# M594X.net
KiCad netlist of a schematic drawn in EAGLE
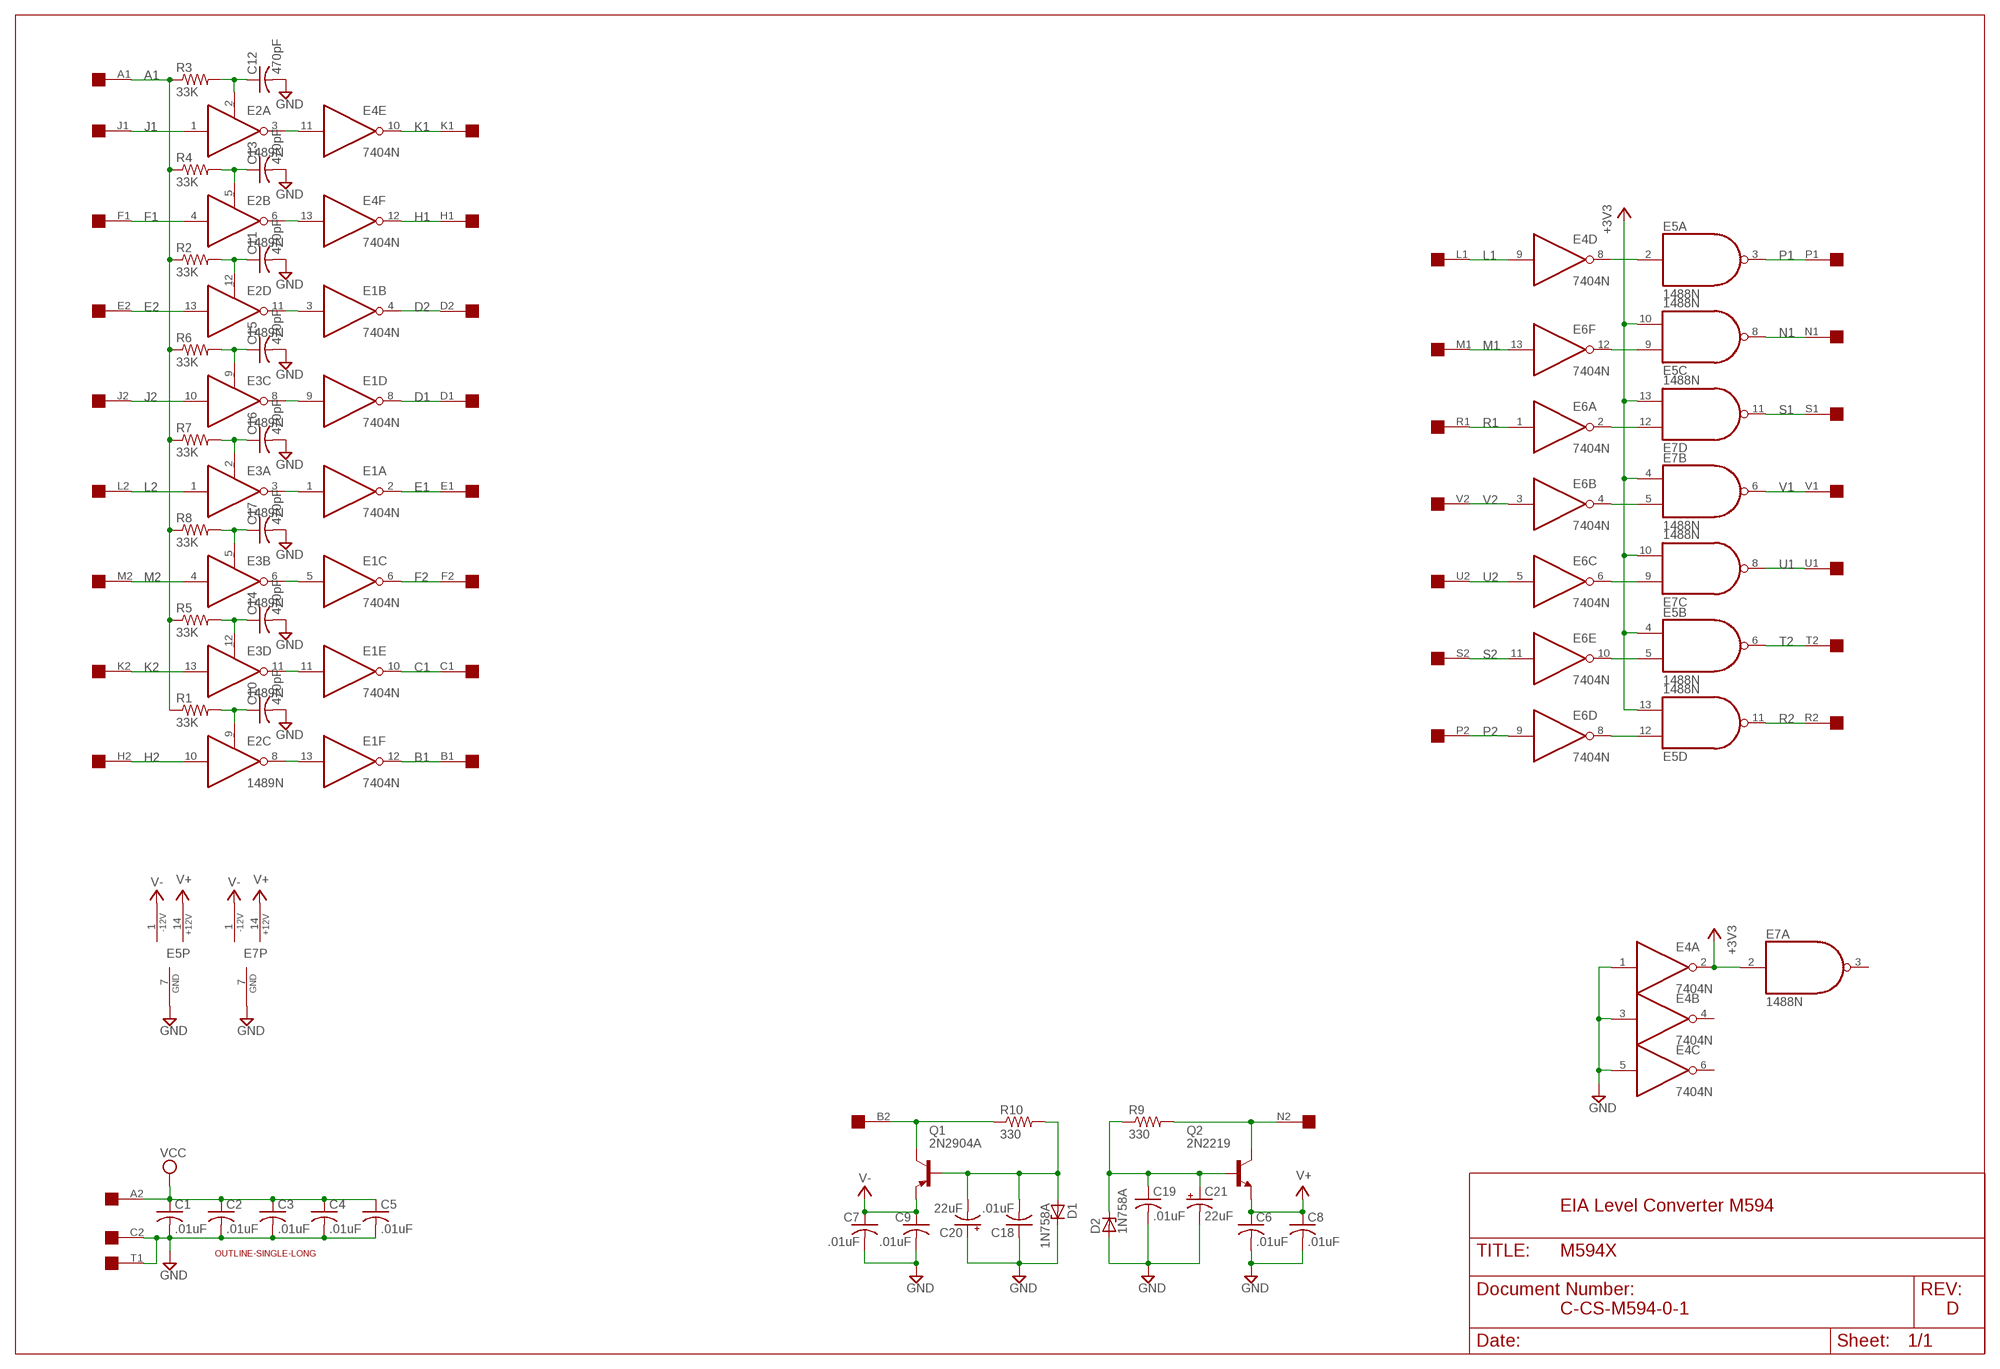
[diagram p0: schematic, sheet 1]

(export (version "E")
  (design (tool "Eeschema 10.0.6"))
  (components
    (comp (ref "C1")
      (value ".01uF")
      (footprint "eagle-import:C050-025X075")
      (libsource (lib "eagle-import") (part "C-US050-025X075"))
    )
    (comp (ref "C2")
      (value ".01uF")
      (footprint "eagle-import:C050-025X075")
      (libsource (lib "eagle-import") (part "C-US050-025X075"))
    )
    (comp (ref "C3")
      (value ".01uF")
      (footprint "eagle-import:C050-025X075")
      (libsource (lib "eagle-import") (part "C-US050-025X075"))
    )
    (comp (ref "C4")
      (value ".01uF")
      (footprint "eagle-import:C050-025X075")
      (libsource (lib "eagle-import") (part "C-US050-025X075"))
    )
    (comp (ref "C5")
      (value ".01uF")
      (footprint "eagle-import:C050-025X075")
      (libsource (lib "eagle-import") (part "C-US050-025X075"))
    )
    (comp (ref "C6")
      (value ".01uF")
      (footprint "eagle-import:C050-025X075")
      (libsource (lib "eagle-import") (part "C-US050-025X075"))
    )
    (comp (ref "C7")
      (value ".01uF")
      (footprint "eagle-import:C050-025X075")
      (libsource (lib "eagle-import") (part "C-US050-025X075"))
    )
    (comp (ref "C8")
      (value ".01uF")
      (footprint "eagle-import:C050-025X075")
      (libsource (lib "eagle-import") (part "C-US050-025X075"))
    )
    (comp (ref "C9")
      (value ".01uF")
      (footprint "eagle-import:C050-025X075")
      (libsource (lib "eagle-import") (part "C-US050-025X075"))
    )
    (comp (ref "C10")
      (value "470pF")
      (footprint "eagle-import:C075-032X103")
      (libsource (lib "eagle-import") (part "C-US075-032X103"))
    )
    (comp (ref "C11")
      (value "470pF")
      (footprint "eagle-import:C075-032X103")
      (libsource (lib "eagle-import") (part "C-US075-032X103"))
    )
    (comp (ref "C12")
      (value "470pF")
      (footprint "eagle-import:C075-032X103")
      (libsource (lib "eagle-import") (part "C-US075-032X103"))
    )
    (comp (ref "C13")
      (value "470pF")
      (footprint "eagle-import:C075-032X103")
      (libsource (lib "eagle-import") (part "C-US075-032X103"))
    )
    (comp (ref "C14")
      (value "470pF")
      (footprint "eagle-import:C075-032X103")
      (libsource (lib "eagle-import") (part "C-US075-032X103"))
    )
    (comp (ref "C15")
      (value "470pF")
      (footprint "eagle-import:C075-032X103")
      (libsource (lib "eagle-import") (part "C-US075-032X103"))
    )
    (comp (ref "C16")
      (value "470pF")
      (footprint "eagle-import:C075-032X103")
      (libsource (lib "eagle-import") (part "C-US075-032X103"))
    )
    (comp (ref "C17")
      (value "470pF")
      (footprint "eagle-import:C075-032X103")
      (libsource (lib "eagle-import") (part "C-US075-032X103"))
    )
    (comp (ref "C18")
      (value ".01uF")
      (footprint "eagle-import:C050-025X075")
      (libsource (lib "eagle-import") (part "C-US050-025X075"))
    )
    (comp (ref "C19")
      (value ".01uF")
      (footprint "eagle-import:C050-025X075")
      (libsource (lib "eagle-import") (part "C-US050-025X075"))
    )
    (comp (ref "C20")
      (value "22uF")
      (footprint "eagle-import:E12-8")
      (libsource (lib "eagle-import") (part "CPOL-USE20-8AXIAL"))
    )
    (comp (ref "C21")
      (value "22uF")
      (footprint "eagle-import:E12-8")
      (libsource (lib "eagle-import") (part "CPOL-USE20-8AXIAL"))
    )
    (comp (ref "D1")
      (value "1N758A")
      (footprint "eagle-import:DO35Z10")
      (libsource (lib "eagle-import") (part "ZENER-DIODEDO35Z10"))
    )
    (comp (ref "D2")
      (value "1N758A")
      (footprint "eagle-import:DO35Z10")
      (libsource (lib "eagle-import") (part "ZENER-DIODEDO35Z10"))
    )
    (comp (ref "E1")
      (value "7404N")
      (footprint "eagle-import:DIL14")
      (libsource (lib "eagle-import") (part "7404N"))
    )
    (comp (ref "E2")
      (value "1489N")
      (footprint "eagle-import:DIL14")
      (libsource (lib "eagle-import") (part "1489N"))
    )
    (comp (ref "E3")
      (value "1489N")
      (footprint "eagle-import:DIL14")
      (libsource (lib "eagle-import") (part "1489N"))
    )
    (comp (ref "E4")
      (value "7404N")
      (footprint "eagle-import:DIL14")
      (libsource (lib "eagle-import") (part "7404N"))
    )
    (comp (ref "E5")
      (value "1488N")
      (footprint "eagle-import:DIL14")
      (libsource (lib "eagle-import") (part "1488N"))
    )
    (comp (ref "E6")
      (value "7404N")
      (footprint "eagle-import:DIL14")
      (libsource (lib "eagle-import") (part "7404N"))
    )
    (comp (ref "E7")
      (value "1488N")
      (footprint "eagle-import:DIL14")
      (libsource (lib "eagle-import") (part "1488N"))
    )
    (comp (ref "Q1")
      (value "2N2904A")
      (footprint "eagle-import:TO5")
      (libsource (lib "eagle-import") (part "-PNP-TO5"))
    )
    (comp (ref "Q2")
      (value "2N2219")
      (footprint "eagle-import:TO5")
      (libsource (lib "eagle-import") (part "-NPN-TO5"))
    )
    (comp (ref "R1")
      (value "33K")
      (footprint "eagle-import:0207_10")
      (libsource (lib "eagle-import") (part "R-US_0207/10"))
    )
    (comp (ref "R2")
      (value "33K")
      (footprint "eagle-import:0207_10")
      (libsource (lib "eagle-import") (part "R-US_0207/10"))
    )
    (comp (ref "R3")
      (value "33K")
      (footprint "eagle-import:0207_10")
      (libsource (lib "eagle-import") (part "R-US_0207/10"))
    )
    (comp (ref "R4")
      (value "33K")
      (footprint "eagle-import:0207_10")
      (libsource (lib "eagle-import") (part "R-US_0207/10"))
    )
    (comp (ref "R5")
      (value "33K")
      (footprint "eagle-import:0207_10")
      (libsource (lib "eagle-import") (part "R-US_0207/10"))
    )
    (comp (ref "R6")
      (value "33K")
      (footprint "eagle-import:0207_10")
      (libsource (lib "eagle-import") (part "R-US_0207/10"))
    )
    (comp (ref "R7")
      (value "33K")
      (footprint "eagle-import:0207_10")
      (libsource (lib "eagle-import") (part "R-US_0207/10"))
    )
    (comp (ref "R8")
      (value "33K")
      (footprint "eagle-import:0207_10")
      (libsource (lib "eagle-import") (part "R-US_0207/10"))
    )
    (comp (ref "R9")
      (value "330")
      (footprint "eagle-import:0207_10")
      (libsource (lib "eagle-import") (part "R-US_0207/10"))
    )
    (comp (ref "R10")
      (value "330")
      (footprint "eagle-import:0207_10")
      (libsource (lib "eagle-import") (part "R-US_0207/10"))
    )
    (comp (ref "U$1")
      (value "OUTLINE-SINGLE-LONG")
      (footprint "eagle-import:SINGLE-LONG")
      (libsource (lib "eagle-import") (part "OUTLINE-SINGLE-LONG"))
    )
    (comp (ref "U$2")
      (value "SINGLE")
      (footprint "eagle-import:EDGE-CON2")
      (libsource (lib "eagle-import") (part "SINGLE"))
    )
  )
  (nets
    (net (code "1") (name "+3V3") (class "Default")
      (node (ref "E4") (pin "2") (pinfunction "O_2") (pintype "output"))
      (node (ref "E5") (pin "10") (pinfunction "I1_10") (pintype "input"))
      (node (ref "E5") (pin "13") (pinfunction "I1_13") (pintype "input"))
      (node (ref "E5") (pin "4") (pinfunction "I0_4") (pintype "input"))
      (node (ref "E7") (pin "10") (pinfunction "I1_10") (pintype "input"))
      (node (ref "E7") (pin "13") (pinfunction "I1_13") (pintype "input"))
      (node (ref "E7") (pin "2") (pinfunction "I_2") (pintype "input"))
      (node (ref "E7") (pin "4") (pinfunction "I0_4") (pintype "input"))
    )
    (net (code "2") (name "/A1") (class "Default")
      (node (ref "R1") (pin "1") (pinfunction "1_1") (pintype "passive"))
      (node (ref "R2") (pin "1") (pinfunction "1_1") (pintype "passive"))
      (node (ref "R3") (pin "1") (pinfunction "1_1") (pintype "passive"))
      (node (ref "R4") (pin "1") (pinfunction "1_1") (pintype "passive"))
      (node (ref "R5") (pin "1") (pinfunction "1_1") (pintype "passive"))
      (node (ref "R6") (pin "1") (pinfunction "1_1") (pintype "passive"))
      (node (ref "R7") (pin "1") (pinfunction "1_1") (pintype "passive"))
      (node (ref "R8") (pin "1") (pinfunction "1_1") (pintype "passive"))
      (node (ref "U$2") (pin "A1") (pinfunction "1_A1") (pintype "bidirectional"))
    )
    (net (code "3") (name "/B1") (class "Default")
      (node (ref "E1") (pin "12") (pinfunction "O_12") (pintype "output"))
      (node (ref "U$2") (pin "B1") (pinfunction "1_B1") (pintype "bidirectional"))
    )
    (net (code "4") (name "/C1") (class "Default")
      (node (ref "E1") (pin "10") (pinfunction "O_10") (pintype "output"))
      (node (ref "U$2") (pin "C1") (pinfunction "1_C1") (pintype "bidirectional"))
    )
    (net (code "5") (name "/D1") (class "Default")
      (node (ref "E1") (pin "8") (pinfunction "O_8") (pintype "output"))
      (node (ref "U$2") (pin "D1") (pinfunction "1_D1") (pintype "bidirectional"))
    )
    (net (code "6") (name "/D2") (class "Default")
      (node (ref "E1") (pin "4") (pinfunction "O_4") (pintype "output"))
      (node (ref "U$2") (pin "D2") (pinfunction "1_D2") (pintype "bidirectional"))
    )
    (net (code "7") (name "/E1") (class "Default")
      (node (ref "E1") (pin "2") (pinfunction "O_2") (pintype "output"))
      (node (ref "U$2") (pin "E1") (pinfunction "1_E1") (pintype "bidirectional"))
    )
    (net (code "8") (name "/E2") (class "Default")
      (node (ref "E2") (pin "13") (pinfunction "I_13") (pintype "input"))
      (node (ref "U$2") (pin "E2") (pinfunction "1_E2") (pintype "bidirectional"))
    )
    (net (code "9") (name "/F1") (class "Default")
      (node (ref "E2") (pin "4") (pinfunction "I_4") (pintype "input"))
      (node (ref "U$2") (pin "F1") (pinfunction "1_F1") (pintype "bidirectional"))
    )
    (net (code "10") (name "/F2") (class "Default")
      (node (ref "E1") (pin "6") (pinfunction "O_6") (pintype "output"))
      (node (ref "U$2") (pin "F2") (pinfunction "1_F2") (pintype "bidirectional"))
    )
    (net (code "11") (name "/H1") (class "Default")
      (node (ref "E4") (pin "12") (pinfunction "O_12") (pintype "output"))
      (node (ref "U$2") (pin "H1") (pinfunction "1_H1") (pintype "bidirectional"))
    )
    (net (code "12") (name "/H2") (class "Default")
      (node (ref "E2") (pin "10") (pinfunction "I_10") (pintype "input"))
      (node (ref "U$2") (pin "H2") (pinfunction "1_H2") (pintype "bidirectional"))
    )
    (net (code "13") (name "/J1") (class "Default")
      (node (ref "E2") (pin "1") (pinfunction "I_1") (pintype "input"))
      (node (ref "U$2") (pin "J1") (pinfunction "1_J1") (pintype "bidirectional"))
    )
    (net (code "14") (name "/J2") (class "Default")
      (node (ref "E3") (pin "10") (pinfunction "I_10") (pintype "input"))
      (node (ref "U$2") (pin "J2") (pinfunction "1_J2") (pintype "bidirectional"))
    )
    (net (code "15") (name "/K1") (class "Default")
      (node (ref "E4") (pin "10") (pinfunction "O_10") (pintype "output"))
      (node (ref "U$2") (pin "K1") (pinfunction "1_K1") (pintype "bidirectional"))
    )
    (net (code "16") (name "/K2") (class "Default")
      (node (ref "E3") (pin "13") (pinfunction "I_13") (pintype "input"))
      (node (ref "U$2") (pin "K2") (pinfunction "1_K2") (pintype "bidirectional"))
    )
    (net (code "17") (name "/L1") (class "Default")
      (node (ref "E4") (pin "9") (pinfunction "I_9") (pintype "input"))
      (node (ref "U$2") (pin "L1") (pinfunction "1_L1") (pintype "bidirectional"))
    )
    (net (code "18") (name "/L2") (class "Default")
      (node (ref "E3") (pin "1") (pinfunction "I_1") (pintype "input"))
      (node (ref "U$2") (pin "L2") (pinfunction "1_L2") (pintype "bidirectional"))
    )
    (net (code "19") (name "/M1") (class "Default")
      (node (ref "E6") (pin "13") (pinfunction "I_13") (pintype "input"))
      (node (ref "U$2") (pin "M1") (pinfunction "1_M1") (pintype "bidirectional"))
    )
    (net (code "20") (name "/M2") (class "Default")
      (node (ref "E3") (pin "4") (pinfunction "I_4") (pintype "input"))
      (node (ref "U$2") (pin "M2") (pinfunction "1_M2") (pintype "bidirectional"))
    )
    (net (code "21") (name "/N1") (class "Default")
      (node (ref "E5") (pin "8") (pinfunction "O_8") (pintype "output"))
      (node (ref "U$2") (pin "N1") (pinfunction "1_N1") (pintype "bidirectional"))
    )
    (net (code "22") (name "/P1") (class "Default")
      (node (ref "E5") (pin "3") (pinfunction "O_3") (pintype "output"))
      (node (ref "U$2") (pin "P1") (pinfunction "1_P1") (pintype "bidirectional"))
    )
    (net (code "23") (name "/P2") (class "Default")
      (node (ref "E6") (pin "9") (pinfunction "I_9") (pintype "input"))
      (node (ref "U$2") (pin "P2") (pinfunction "1_P2") (pintype "bidirectional"))
    )
    (net (code "24") (name "/R1") (class "Default")
      (node (ref "E6") (pin "1") (pinfunction "I_1") (pintype "input"))
      (node (ref "U$2") (pin "R1") (pinfunction "1_R1") (pintype "bidirectional"))
    )
    (net (code "25") (name "/R2") (class "Default")
      (node (ref "E5") (pin "11") (pinfunction "O_11") (pintype "output"))
      (node (ref "U$2") (pin "R2") (pinfunction "1_R2") (pintype "bidirectional"))
    )
    (net (code "26") (name "/S1") (class "Default")
      (node (ref "E7") (pin "11") (pinfunction "O_11") (pintype "output"))
      (node (ref "U$2") (pin "S1") (pinfunction "1_S1") (pintype "bidirectional"))
    )
    (net (code "27") (name "/S2") (class "Default")
      (node (ref "E6") (pin "11") (pinfunction "I_11") (pintype "input"))
      (node (ref "U$2") (pin "S2") (pinfunction "1_S2") (pintype "bidirectional"))
    )
    (net (code "28") (name "/T2") (class "Default")
      (node (ref "E5") (pin "6") (pinfunction "O_6") (pintype "output"))
      (node (ref "U$2") (pin "T2") (pinfunction "1_T2") (pintype "bidirectional"))
    )
    (net (code "29") (name "/U1") (class "Default")
      (node (ref "E7") (pin "8") (pinfunction "O_8") (pintype "output"))
      (node (ref "U$2") (pin "U1") (pinfunction "1_U1") (pintype "bidirectional"))
    )
    (net (code "30") (name "/U2") (class "Default")
      (node (ref "E6") (pin "5") (pinfunction "I_5") (pintype "input"))
      (node (ref "U$2") (pin "U2") (pinfunction "1_U2") (pintype "bidirectional"))
    )
    (net (code "31") (name "/V1") (class "Default")
      (node (ref "E7") (pin "6") (pinfunction "O_6") (pintype "output"))
      (node (ref "U$2") (pin "V1") (pinfunction "1_V1") (pintype "bidirectional"))
    )
    (net (code "32") (name "/V2") (class "Default")
      (node (ref "E6") (pin "3") (pinfunction "I_3") (pintype "input"))
      (node (ref "U$2") (pin "V2") (pinfunction "1_V2") (pintype "bidirectional"))
    )
    (net (code "33") (name "GND") (class "Default")
      (node (ref "C1") (pin "2") (pinfunction "2_2") (pintype "passive"))
      (node (ref "C10") (pin "2") (pinfunction "2_2") (pintype "passive"))
      (node (ref "C11") (pin "2") (pinfunction "2_2") (pintype "passive"))
      (node (ref "C12") (pin "2") (pinfunction "2_2") (pintype "passive"))
      (node (ref "C13") (pin "2") (pinfunction "2_2") (pintype "passive"))
      (node (ref "C14") (pin "2") (pinfunction "2_2") (pintype "passive"))
      (node (ref "C15") (pin "2") (pinfunction "2_2") (pintype "passive"))
      (node (ref "C16") (pin "2") (pinfunction "2_2") (pintype "passive"))
      (node (ref "C17") (pin "2") (pinfunction "2_2") (pintype "passive"))
      (node (ref "C18") (pin "1") (pinfunction "1_1") (pintype "passive"))
      (node (ref "C19") (pin "2") (pinfunction "2_2") (pintype "passive"))
      (node (ref "C2") (pin "2") (pinfunction "2_2") (pintype "passive"))
      (node (ref "C20") (pin "+") (pinfunction "+_+") (pintype "passive"))
      (node (ref "C21") (pin "-") (pinfunction "-_-") (pintype "passive"))
      (node (ref "C3") (pin "2") (pinfunction "2_2") (pintype "passive"))
      (node (ref "C4") (pin "2") (pinfunction "2_2") (pintype "passive"))
      (node (ref "C5") (pin "2") (pinfunction "2_2") (pintype "passive"))
      (node (ref "C6") (pin "2") (pinfunction "2_2") (pintype "passive"))
      (node (ref "C7") (pin "2") (pinfunction "2_2") (pintype "passive"))
      (node (ref "C8") (pin "2") (pinfunction "2_2") (pintype "passive"))
      (node (ref "C9") (pin "2") (pinfunction "2_2") (pintype "passive"))
      (node (ref "D1") (pin "C") (pinfunction "C_C") (pintype "passive"))
      (node (ref "D2") (pin "A") (pinfunction "A_A") (pintype "passive"))
      (node (ref "E4") (pin "1") (pinfunction "I_1") (pintype "input"))
      (node (ref "E4") (pin "3") (pinfunction "I_3") (pintype "input"))
      (node (ref "E4") (pin "5") (pinfunction "I_5") (pintype "input"))
      (node (ref "E5") (pin "7") (pinfunction "GND_7") (pintype "power_in"))
      (node (ref "E7") (pin "7") (pinfunction "GND_7") (pintype "power_in"))
      (node (ref "U$2") (pin "C2") (pinfunction "1_C2") (pintype "bidirectional"))
      (node (ref "U$2") (pin "T1") (pinfunction "1_T1") (pintype "bidirectional"))
    )
    (net (code "34") (name "Net-(E1A-I)") (class "Default")
      (node (ref "E1") (pin "1") (pinfunction "I_1") (pintype "input"))
      (node (ref "E3") (pin "3") (pinfunction "O_3") (pintype "output"))
    )
    (net (code "35") (name "Net-(E1B-I)") (class "Default")
      (node (ref "E1") (pin "3") (pinfunction "I_3") (pintype "input"))
      (node (ref "E2") (pin "11") (pinfunction "O_11") (pintype "output"))
    )
    (net (code "36") (name "Net-(E1C-I)") (class "Default")
      (node (ref "E1") (pin "5") (pinfunction "I_5") (pintype "input"))
      (node (ref "E3") (pin "6") (pinfunction "O_6") (pintype "output"))
    )
    (net (code "37") (name "Net-(E1D-I)") (class "Default")
      (node (ref "E1") (pin "9") (pinfunction "I_9") (pintype "input"))
      (node (ref "E3") (pin "8") (pinfunction "O_8") (pintype "output"))
    )
    (net (code "38") (name "Net-(E1E-I)") (class "Default")
      (node (ref "E1") (pin "11") (pinfunction "I_11") (pintype "input"))
      (node (ref "E3") (pin "11") (pinfunction "O_11") (pintype "output"))
    )
    (net (code "39") (name "Net-(E1F-I)") (class "Default")
      (node (ref "E1") (pin "13") (pinfunction "I_13") (pintype "input"))
      (node (ref "E2") (pin "8") (pinfunction "O_8") (pintype "output"))
    )
    (net (code "40") (name "Net-(E2A-O)") (class "Default")
      (node (ref "E2") (pin "3") (pinfunction "O_3") (pintype "output"))
      (node (ref "E4") (pin "11") (pinfunction "I_11") (pintype "input"))
    )
    (net (code "41") (name "Net-(E2A-RC)") (class "Default")
      (node (ref "C12") (pin "1") (pinfunction "1_1") (pintype "passive"))
      (node (ref "E2") (pin "2") (pinfunction "RC_2") (pintype "input"))
      (node (ref "R3") (pin "2") (pinfunction "2_2") (pintype "passive"))
    )
    (net (code "42") (name "Net-(E2B-O)") (class "Default")
      (node (ref "E2") (pin "6") (pinfunction "O_6") (pintype "output"))
      (node (ref "E4") (pin "13") (pinfunction "I_13") (pintype "input"))
    )
    (net (code "43") (name "Net-(E2B-RC)") (class "Default")
      (node (ref "C13") (pin "1") (pinfunction "1_1") (pintype "passive"))
      (node (ref "E2") (pin "5") (pinfunction "RC_5") (pintype "input"))
      (node (ref "R4") (pin "2") (pinfunction "2_2") (pintype "passive"))
    )
    (net (code "44") (name "Net-(E2C-RC)") (class "Default")
      (node (ref "C10") (pin "1") (pinfunction "1_1") (pintype "passive"))
      (node (ref "E2") (pin "9") (pinfunction "RC_9") (pintype "input"))
      (node (ref "R1") (pin "2") (pinfunction "2_2") (pintype "passive"))
    )
    (net (code "45") (name "Net-(E2D-RC)") (class "Default")
      (node (ref "C11") (pin "1") (pinfunction "1_1") (pintype "passive"))
      (node (ref "E2") (pin "12") (pinfunction "RC_12") (pintype "input"))
      (node (ref "R2") (pin "2") (pinfunction "2_2") (pintype "passive"))
    )
    (net (code "46") (name "Net-(E3A-RC)") (class "Default")
      (node (ref "C16") (pin "1") (pinfunction "1_1") (pintype "passive"))
      (node (ref "E3") (pin "2") (pinfunction "RC_2") (pintype "input"))
      (node (ref "R7") (pin "2") (pinfunction "2_2") (pintype "passive"))
    )
    (net (code "47") (name "Net-(E3B-RC)") (class "Default")
      (node (ref "C17") (pin "1") (pinfunction "1_1") (pintype "passive"))
      (node (ref "E3") (pin "5") (pinfunction "RC_5") (pintype "input"))
      (node (ref "R8") (pin "2") (pinfunction "2_2") (pintype "passive"))
    )
    (net (code "48") (name "Net-(E3C-RC)") (class "Default")
      (node (ref "C15") (pin "1") (pinfunction "1_1") (pintype "passive"))
      (node (ref "E3") (pin "9") (pinfunction "RC_9") (pintype "input"))
      (node (ref "R6") (pin "2") (pinfunction "2_2") (pintype "passive"))
    )
    (net (code "49") (name "Net-(E3D-RC)") (class "Default")
      (node (ref "C14") (pin "1") (pinfunction "1_1") (pintype "passive"))
      (node (ref "E3") (pin "12") (pinfunction "RC_12") (pintype "input"))
      (node (ref "R5") (pin "2") (pinfunction "2_2") (pintype "passive"))
    )
    (net (code "50") (name "Net-(E4D-O)") (class "Default")
      (node (ref "E4") (pin "8") (pinfunction "O_8") (pintype "output"))
      (node (ref "E5") (pin "2") (pinfunction "I_2") (pintype "input"))
    )
    (net (code "51") (name "Net-(E5B-I1)") (class "Default")
      (node (ref "E5") (pin "5") (pinfunction "I1_5") (pintype "input"))
      (node (ref "E6") (pin "10") (pinfunction "O_10") (pintype "output"))
    )
    (net (code "52") (name "Net-(E5C-I0)") (class "Default")
      (node (ref "E5") (pin "9") (pinfunction "I0_9") (pintype "input"))
      (node (ref "E6") (pin "12") (pinfunction "O_12") (pintype "output"))
    )
    (net (code "53") (name "Net-(E5D-I0)") (class "Default")
      (node (ref "E5") (pin "12") (pinfunction "I0_12") (pintype "input"))
      (node (ref "E6") (pin "8") (pinfunction "O_8") (pintype "output"))
    )
    (net (code "54") (name "Net-(E6A-O)") (class "Default")
      (node (ref "E6") (pin "2") (pinfunction "O_2") (pintype "output"))
      (node (ref "E7") (pin "12") (pinfunction "I0_12") (pintype "input"))
    )
    (net (code "55") (name "Net-(E6B-O)") (class "Default")
      (node (ref "E6") (pin "4") (pinfunction "O_4") (pintype "output"))
      (node (ref "E7") (pin "5") (pinfunction "I1_5") (pintype "input"))
    )
    (net (code "56") (name "Net-(E6C-O)") (class "Default")
      (node (ref "E6") (pin "6") (pinfunction "O_6") (pintype "output"))
      (node (ref "E7") (pin "9") (pinfunction "I0_9") (pintype "input"))
    )
    (net (code "57") (name "Net-(Q1-B)") (class "Default")
      (node (ref "C18") (pin "2") (pinfunction "2_2") (pintype "passive"))
      (node (ref "C20") (pin "-") (pinfunction "-_-") (pintype "passive"))
      (node (ref "D1") (pin "A") (pinfunction "A_A") (pintype "passive"))
      (node (ref "Q1") (pin "2") (pinfunction "B_2") (pintype "passive"))
      (node (ref "R10") (pin "2") (pinfunction "2_2") (pintype "passive"))
    )
    (net (code "58") (name "Net-(Q1-C)") (class "Default")
      (node (ref "Q1") (pin "3") (pinfunction "C_3") (pintype "passive"))
      (node (ref "R10") (pin "1") (pinfunction "1_1") (pintype "passive"))
      (node (ref "U$2") (pin "B2") (pinfunction "1_B2") (pintype "bidirectional"))
    )
    (net (code "59") (name "Net-(Q2-B)") (class "Default")
      (node (ref "C19") (pin "1") (pinfunction "1_1") (pintype "passive"))
      (node (ref "C21") (pin "+") (pinfunction "+_+") (pintype "passive"))
      (node (ref "D2") (pin "C") (pinfunction "C_C") (pintype "passive"))
      (node (ref "Q2") (pin "2") (pinfunction "B_2") (pintype "passive"))
      (node (ref "R9") (pin "1") (pinfunction "1_1") (pintype "passive"))
    )
    (net (code "60") (name "Net-(Q2-C)") (class "Default")
      (node (ref "Q2") (pin "3") (pinfunction "C_3") (pintype "passive"))
      (node (ref "R9") (pin "2") (pinfunction "2_2") (pintype "passive"))
      (node (ref "U$2") (pin "N2") (pinfunction "1_N2") (pintype "bidirectional"))
    )
    (net (code "61") (name "V+") (class "Default")
      (node (ref "C6") (pin "1") (pinfunction "1_1") (pintype "passive"))
      (node (ref "C8") (pin "1") (pinfunction "1_1") (pintype "passive"))
      (node (ref "E5") (pin "14") (pinfunction "+12V_14") (pintype "power_in"))
      (node (ref "E7") (pin "14") (pinfunction "+12V_14") (pintype "power_in"))
      (node (ref "Q2") (pin "1") (pinfunction "E_1") (pintype "passive"))
    )
    (net (code "62") (name "V-") (class "Default")
      (node (ref "C7") (pin "1") (pinfunction "1_1") (pintype "passive"))
      (node (ref "C9") (pin "1") (pinfunction "1_1") (pintype "passive"))
      (node (ref "E5") (pin "1") (pinfunction "-12V_1") (pintype "power_in"))
      (node (ref "E7") (pin "1") (pinfunction "-12V_1") (pintype "power_in"))
      (node (ref "Q1") (pin "1") (pinfunction "E_1") (pintype "passive"))
    )
    (net (code "63") (name "VCC") (class "Default")
      (node (ref "C1") (pin "1") (pinfunction "1_1") (pintype "passive"))
      (node (ref "C2") (pin "1") (pinfunction "1_1") (pintype "passive"))
      (node (ref "C3") (pin "1") (pinfunction "1_1") (pintype "passive"))
      (node (ref "C4") (pin "1") (pinfunction "1_1") (pintype "passive"))
      (node (ref "C5") (pin "1") (pinfunction "1_1") (pintype "passive"))
      (node (ref "U$2") (pin "A2") (pinfunction "1_A2") (pintype "bidirectional"))
    )
    (net (code "64") (name "unconnected-(E4B-O-Pad4)") (class "Default")
      (node (ref "E4") (pin "4") (pinfunction "O_4") (pintype "output"))
    )
    (net (code "65") (name "unconnected-(E4C-O-Pad6)") (class "Default")
      (node (ref "E4") (pin "6") (pinfunction "O_6") (pintype "output"))
    )
    (net (code "66") (name "unconnected-(E7A-O-Pad3)") (class "Default")
      (node (ref "E7") (pin "3") (pinfunction "O_3") (pintype "output"))
    )
  )
)
